# Adafruit_Chainable_DS18B20_Extender_Brea.net
KiCad netlist of a schematic drawn in EAGLE
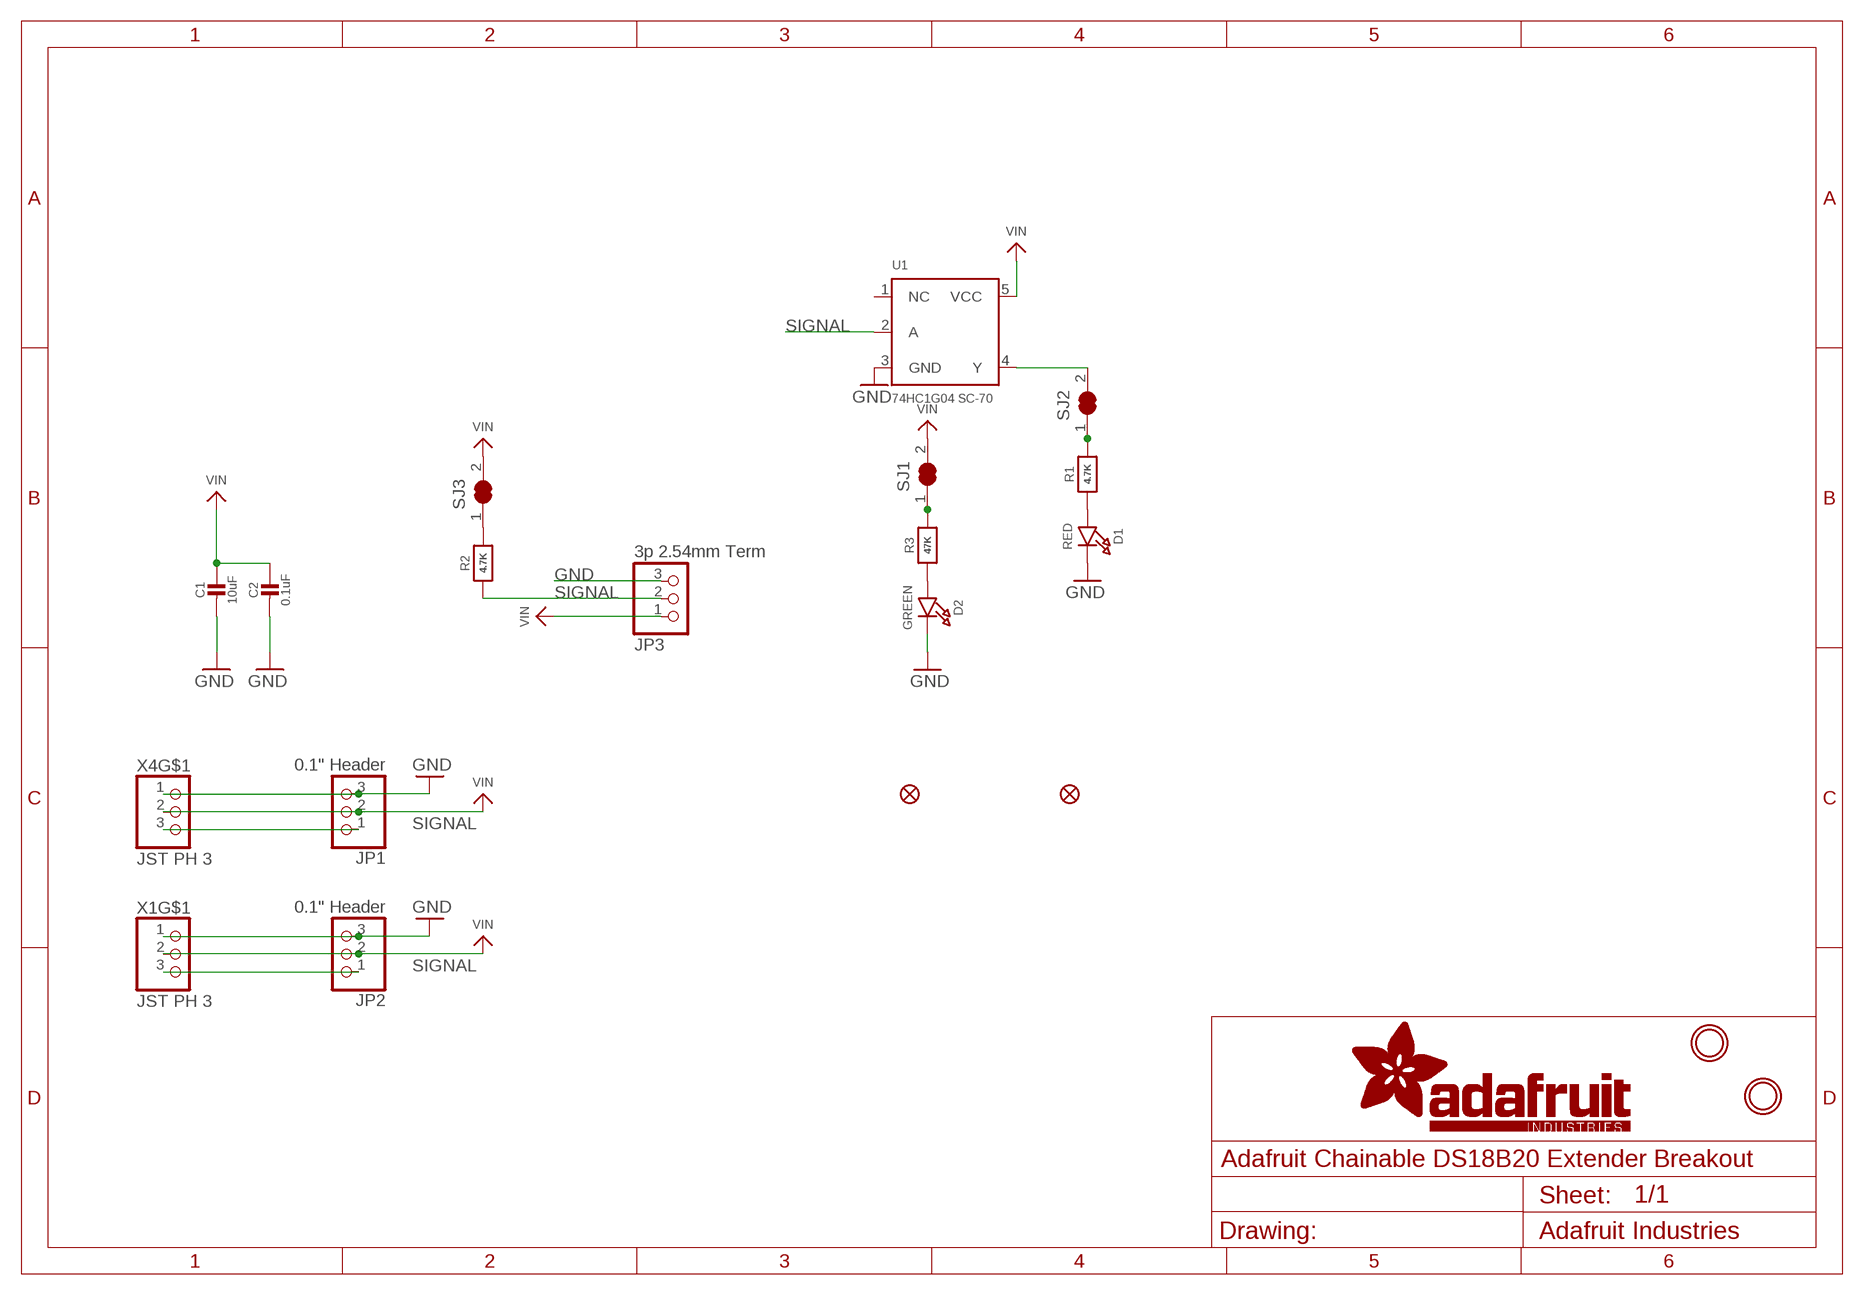
[diagram p0: schematic, sheet 1]

(export (version "E")
  (design (tool "Eeschema 10.0.6"))
  (components
    (comp (ref "C1")
      (value "10uF")
      (footprint "eagle-import:0805-NO")
      (libsource (lib "eagle-import") (part "CAP_CERAMIC0805-NOOUTLINE"))
    )
    (comp (ref "C2")
      (value "0.1uF")
      (footprint "eagle-import:0603-NO")
      (libsource (lib "eagle-import") (part "CAP_CERAMIC0603_NO"))
    )
    (comp (ref "D1")
      (value "RED")
      (footprint "eagle-import:CHIPLED_0603_NOOUTLINE")
      (libsource (lib "eagle-import") (part "LED0603_NOOUTLINE"))
    )
    (comp (ref "D2")
      (value "GREEN")
      (footprint "eagle-import:CHIPLED_0603_NOOUTLINE")
      (libsource (lib "eagle-import") (part "LED0603_NOOUTLINE"))
    )
    (comp (ref "FID2")
      (value "FIDUCIAL_1MM")
      (footprint "eagle-import:FIDUCIAL_1MM")
      (libsource (lib "eagle-import") (part "FIDUCIAL_1MM"))
    )
    (comp (ref "FID3")
      (value "FIDUCIAL_1MM")
      (footprint "eagle-import:FIDUCIAL_1MM")
      (libsource (lib "eagle-import") (part "FIDUCIAL_1MM"))
    )
    (comp (ref "JP1")
      (value "0.1\" Header")
      (footprint "eagle-import:1X03_OVAL")
      (libsource (lib "eagle-import") (part "HEADER-1X3"))
    )
    (comp (ref "JP2")
      (value "0.1\" Header")
      (footprint "eagle-import:1X03_OVAL")
      (libsource (lib "eagle-import") (part "HEADER-1X3"))
    )
    (comp (ref "JP3")
      (value "3p 2.54mm Term")
      (footprint "eagle-import:1X03_2.54MMTERMINAL")
      (libsource (lib "eagle-import") (part "HEADER-1X3_254TERM"))
    )
    (comp (ref "R1")
      (value "4.7K")
      (footprint "eagle-import:0603-NO")
      (libsource (lib "eagle-import") (part "RESISTOR_0603_NOOUT"))
    )
    (comp (ref "R2")
      (value "4.7K")
      (footprint "eagle-import:0603-NO")
      (libsource (lib "eagle-import") (part "RESISTOR_0603_NOOUT"))
    )
    (comp (ref "R3")
      (value "47K")
      (footprint "eagle-import:0603-NO")
      (libsource (lib "eagle-import") (part "RESISTOR_0603_NOOUT"))
    )
    (comp (ref "SJ1")
      (value "SOLDERJUMPER_CLOSED")
      (footprint "eagle-import:SOLDERJUMPER_CLOSEDWIRE")
      (libsource (lib "eagle-import") (part "SOLDERJUMPER_CLOSED"))
    )
    (comp (ref "SJ2")
      (value "SOLDERJUMPER_CLOSED")
      (footprint "eagle-import:SOLDERJUMPER_CLOSEDWIRE")
      (libsource (lib "eagle-import") (part "SOLDERJUMPER_CLOSED"))
    )
    (comp (ref "SJ3")
      (value "SOLDERJUMPER_CLOSED")
      (footprint "eagle-import:SOLDERJUMPER_CLOSEDWIRE")
      (libsource (lib "eagle-import") (part "SOLDERJUMPER_CLOSED"))
    )
    (comp (ref "U$1")
      (value "MOUNTINGHOLE2.0")
      (footprint "eagle-import:MOUNTINGHOLE_2.0_PLATED")
      (libsource (lib "eagle-import") (part "MOUNTINGHOLE2.0"))
    )
    (comp (ref "U$8")
      (value "MOUNTINGHOLE2.0")
      (footprint "eagle-import:MOUNTINGHOLE_2.0_PLATED")
      (libsource (lib "eagle-import") (part "MOUNTINGHOLE2.0"))
    )
    (comp (ref "U1")
      (value "74HC1G04 SC-70")
      (footprint "eagle-import:SC70-5")
      (libsource (lib "eagle-import") (part "74LVC1G04SC-70"))
    )
    (comp (ref "X1")
      (value "JST PH 3")
      (footprint "eagle-import:JSTPH3")
      (libsource (lib "eagle-import") (part "CON_JST_PH_3PIN"))
    )
    (comp (ref "X4")
      (value "JST PH 3")
      (footprint "eagle-import:JSTPH3")
      (libsource (lib "eagle-import") (part "CON_JST_PH_3PIN"))
    )
  )
  (nets
    (net (code "1") (name "/SIGNAL") (class "Default")
      (node (ref "JP1") (pin "1") (pinfunction "1_1") (pintype "passive"))
      (node (ref "JP2") (pin "1") (pinfunction "1_1") (pintype "passive"))
      (node (ref "JP3") (pin "2") (pinfunction "2_2") (pintype "passive"))
      (node (ref "R2") (pin "1") (pinfunction "1_1") (pintype "passive"))
      (node (ref "U1") (pin "2") (pinfunction "A_2") (pintype "bidirectional"))
      (node (ref "X1") (pin "3") (pinfunction "3_3") (pintype "passive"))
      (node (ref "X4") (pin "3") (pinfunction "3_3") (pintype "passive"))
    )
    (net (code "2") (name "GND") (class "Default")
      (node (ref "C1") (pin "2") (pinfunction "2_2") (pintype "passive"))
      (node (ref "C2") (pin "2") (pinfunction "2_2") (pintype "passive"))
      (node (ref "D1") (pin "C") (pinfunction "C_C") (pintype "passive"))
      (node (ref "D2") (pin "C") (pinfunction "C_C") (pintype "passive"))
      (node (ref "JP1") (pin "3") (pinfunction "3_3") (pintype "passive"))
      (node (ref "JP2") (pin "3") (pinfunction "3_3") (pintype "passive"))
      (node (ref "JP3") (pin "3") (pinfunction "3_3") (pintype "passive"))
      (node (ref "U1") (pin "3") (pinfunction "GND_3") (pintype "power_in"))
      (node (ref "X1") (pin "1") (pinfunction "1_1") (pintype "passive"))
      (node (ref "X4") (pin "1") (pinfunction "1_1") (pintype "passive"))
    )
    (net (code "3") (name "Net-(D1-PadA)") (class "Default")
      (node (ref "D1") (pin "A") (pinfunction "A_A") (pintype "passive"))
      (node (ref "R1") (pin "1") (pinfunction "1_1") (pintype "passive"))
    )
    (net (code "4") (name "Net-(D2-PadA)") (class "Default")
      (node (ref "D2") (pin "A") (pinfunction "A_A") (pintype "passive"))
      (node (ref "R3") (pin "1") (pinfunction "1_1") (pintype "passive"))
    )
    (net (code "5") (name "Net-(R1-Pad2)") (class "Default")
      (node (ref "R1") (pin "2") (pinfunction "2_2") (pintype "passive"))
      (node (ref "SJ2") (pin "1") (pinfunction "1_1") (pintype "passive"))
    )
    (net (code "6") (name "Net-(R2-Pad2)") (class "Default")
      (node (ref "R2") (pin "2") (pinfunction "2_2") (pintype "passive"))
      (node (ref "SJ3") (pin "1") (pinfunction "1_1") (pintype "passive"))
    )
    (net (code "7") (name "Net-(R3-Pad2)") (class "Default")
      (node (ref "R3") (pin "2") (pinfunction "2_2") (pintype "passive"))
      (node (ref "SJ1") (pin "1") (pinfunction "1_1") (pintype "passive"))
    )
    (net (code "8") (name "Net-(U1-Y)") (class "Default")
      (node (ref "SJ2") (pin "2") (pinfunction "2_2") (pintype "passive"))
      (node (ref "U1") (pin "4") (pinfunction "Y_4") (pintype "bidirectional"))
    )
    (net (code "9") (name "VIN") (class "Default")
      (node (ref "C1") (pin "1") (pinfunction "1_1") (pintype "passive"))
      (node (ref "C2") (pin "1") (pinfunction "1_1") (pintype "passive"))
      (node (ref "JP1") (pin "2") (pinfunction "2_2") (pintype "passive"))
      (node (ref "JP2") (pin "2") (pinfunction "2_2") (pintype "passive"))
      (node (ref "JP3") (pin "1") (pinfunction "1_1") (pintype "passive"))
      (node (ref "SJ1") (pin "2") (pinfunction "2_2") (pintype "passive"))
      (node (ref "SJ3") (pin "2") (pinfunction "2_2") (pintype "passive"))
      (node (ref "U1") (pin "5") (pinfunction "VCC_5") (pintype "power_in"))
      (node (ref "X1") (pin "2") (pinfunction "2_2") (pintype "passive"))
      (node (ref "X4") (pin "2") (pinfunction "2_2") (pintype "passive"))
    )
    (net (code "10") (name "unconnected-(U1-NC-Pad1)") (class "Default")
      (node (ref "U1") (pin "1") (pinfunction "NC_1") (pintype "no_connect"))
    )
  )
)
